# Stripline_Driver.net
KiCad netlist of a schematic drawn in Altium Designer
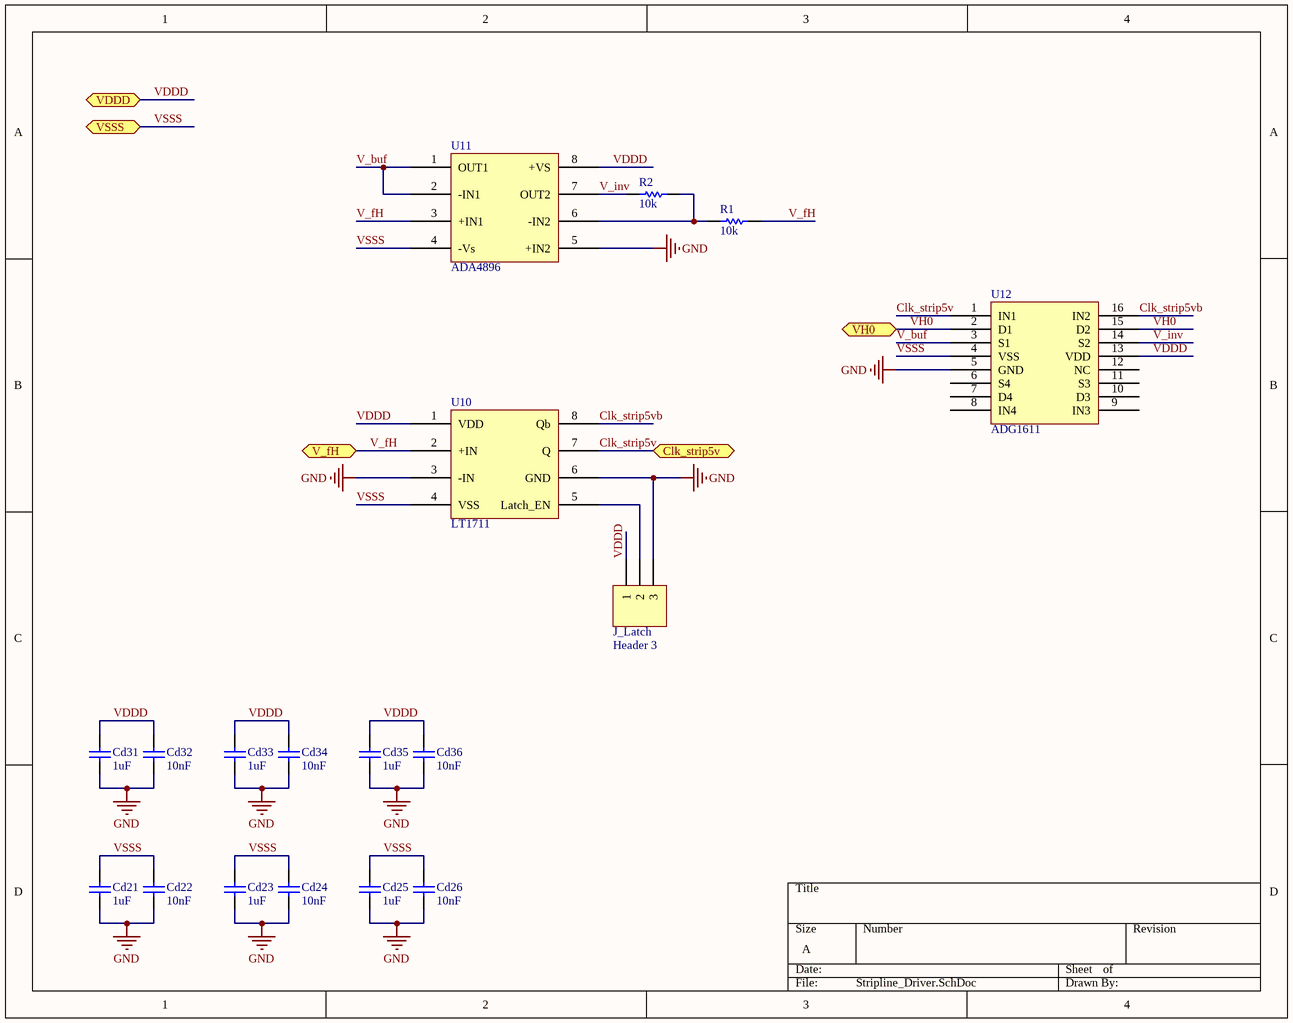
[diagram p0: Stripline_Driver.SchDoc]

(export (version "E")
  (design (tool "Eeschema 10.0.6"))
  (components
    (comp (ref "Cd21")
      (value "1uF")
      (footprint "1608[0603]")
      (description "Capacitor")
      (fields (field (name "Comment") "Cap") (field (name "PUBLISHER") "Altium Limited"))
      (libsource (lib "Miscellaneous Devices") (part "Cap"))
    )
    (comp (ref "Cd22")
      (value "10nF")
      (footprint "1608[0603]")
      (description "Capacitor")
      (fields (field (name "Comment") "Cap") (field (name "PUBLISHER") "Altium Limited"))
      (libsource (lib "Miscellaneous Devices") (part "Cap"))
    )
    (comp (ref "Cd23")
      (value "1uF")
      (footprint "1608[0603]")
      (description "Capacitor")
      (fields (field (name "Comment") "Cap") (field (name "PUBLISHER") "Altium Limited"))
      (libsource (lib "Miscellaneous Devices") (part "Cap"))
    )
    (comp (ref "Cd24")
      (value "10nF")
      (footprint "1608[0603]")
      (description "Capacitor")
      (fields (field (name "Comment") "Cap") (field (name "PUBLISHER") "Altium Limited"))
      (libsource (lib "Miscellaneous Devices") (part "Cap"))
    )
    (comp (ref "Cd25")
      (value "1uF")
      (footprint "1608[0603]")
      (description "Capacitor")
      (fields (field (name "Comment") "Cap") (field (name "PUBLISHER") "Altium Limited"))
      (libsource (lib "Miscellaneous Devices") (part "Cap"))
    )
    (comp (ref "Cd26")
      (value "10nF")
      (footprint "1608[0603]")
      (description "Capacitor")
      (fields (field (name "Comment") "Cap") (field (name "PUBLISHER") "Altium Limited"))
      (libsource (lib "Miscellaneous Devices") (part "Cap"))
    )
    (comp (ref "Cd31")
      (value "1uF")
      (footprint "1608[0603]")
      (description "Capacitor")
      (fields (field (name "Comment") "Cap") (field (name "PUBLISHER") "Altium Limited"))
      (libsource (lib "Miscellaneous Devices") (part "Cap"))
    )
    (comp (ref "Cd32")
      (value "10nF")
      (footprint "1608[0603]")
      (description "Capacitor")
      (fields (field (name "Comment") "Cap") (field (name "PUBLISHER") "Altium Limited"))
      (libsource (lib "Miscellaneous Devices") (part "Cap"))
    )
    (comp (ref "Cd33")
      (value "1uF")
      (footprint "1608[0603]")
      (description "Capacitor")
      (fields (field (name "Comment") "Cap") (field (name "PUBLISHER") "Altium Limited"))
      (libsource (lib "Miscellaneous Devices") (part "Cap"))
    )
    (comp (ref "Cd34")
      (value "10nF")
      (footprint "1608[0603]")
      (description "Capacitor")
      (fields (field (name "Comment") "Cap") (field (name "PUBLISHER") "Altium Limited"))
      (libsource (lib "Miscellaneous Devices") (part "Cap"))
    )
    (comp (ref "Cd35")
      (value "1uF")
      (footprint "1608[0603]")
      (description "Capacitor")
      (fields (field (name "Comment") "Cap") (field (name "PUBLISHER") "Altium Limited"))
      (libsource (lib "Miscellaneous Devices") (part "Cap"))
    )
    (comp (ref "Cd36")
      (value "10nF")
      (footprint "1608[0603]")
      (description "Capacitor")
      (fields (field (name "Comment") "Cap") (field (name "PUBLISHER") "Altium Limited"))
      (libsource (lib "Miscellaneous Devices") (part "Cap"))
    )
    (comp (ref "J_Latch")
      (value "Header 3")
      (footprint "HDR1X3")
      (description "Header, 3-Pin")
      (fields (field (name "PUBLISHER") "Altium Limited"))
      (libsource (lib "Miscellaneous Connectors") (part "Header 3"))
    )
    (comp (ref "R1")
      (value "10k")
      (footprint "1608[0603]")
      (description "Resistor")
      (fields (field (name "Comment") "Res1") (field (name "PUBLISHER") "Altium Limited"))
      (libsource (lib "Miscellaneous Devices") (part "Res1"))
    )
    (comp (ref "R2")
      (value "10k")
      (footprint "1608[0603]")
      (description "Resistor")
      (fields (field (name "Comment") "Res1") (field (name "PUBLISHER") "Altium Limited"))
      (libsource (lib "Miscellaneous Devices") (part "Res1"))
    )
    (comp (ref "U10") (value "LT1711") (footprint "RM-8") (libsource (lib "custom") (part "LT1711")))
    (comp (ref "U11") (value "ADA4896") (footprint "RM-8") (libsource (lib "custom") (part "ADA4862")))
    (comp (ref "U12") (value "ADG1611") (footprint "RU-16") (libsource (lib "custom") (part "ADG1611")))
  )
  (nets
    (net (code "1") (name "/Clk_strip5v") (class "Default")
      (node (ref "U10") (pin "7") (pinfunction "Q_7") (pintype "passive"))
      (node (ref "U12") (pin "1") (pinfunction "IN1_1") (pintype "passive"))
    )
    (net (code "2") (name "/Clk_strip5vb") (class "Default")
      (node (ref "U10") (pin "8") (pinfunction "Qb_8") (pintype "passive"))
      (node (ref "U12") (pin "16") (pinfunction "IN2_16") (pintype "passive"))
    )
    (net (code "3") (name "/VDDD") (class "Default")
      (node (ref "Cd31") (pin "1") (pinfunction "1_1") (pintype "passive"))
      (node (ref "Cd32") (pin "1") (pinfunction "1_1") (pintype "passive"))
      (node (ref "Cd33") (pin "1") (pinfunction "1_1") (pintype "passive"))
      (node (ref "Cd34") (pin "1") (pinfunction "1_1") (pintype "passive"))
      (node (ref "Cd35") (pin "1") (pinfunction "1_1") (pintype "passive"))
      (node (ref "Cd36") (pin "1") (pinfunction "1_1") (pintype "passive"))
      (node (ref "J_Latch") (pin "1") (pinfunction "1_1") (pintype "passive"))
      (node (ref "U10") (pin "1") (pinfunction "VDD_1") (pintype "passive"))
      (node (ref "U11") (pin "8") (pinfunction "+VS_8") (pintype "passive"))
      (node (ref "U12") (pin "13") (pinfunction "VDD_13") (pintype "passive"))
    )
    (net (code "4") (name "/VH0") (class "Default")
      (node (ref "U12") (pin "15") (pinfunction "D2_15") (pintype "passive"))
      (node (ref "U12") (pin "2") (pinfunction "D1_2") (pintype "passive"))
    )
    (net (code "5") (name "/VSSS") (class "Default")
      (node (ref "Cd21") (pin "1") (pinfunction "1_1") (pintype "passive"))
      (node (ref "Cd22") (pin "1") (pinfunction "1_1") (pintype "passive"))
      (node (ref "Cd23") (pin "1") (pinfunction "1_1") (pintype "passive"))
      (node (ref "Cd24") (pin "1") (pinfunction "1_1") (pintype "passive"))
      (node (ref "Cd25") (pin "1") (pinfunction "1_1") (pintype "passive"))
      (node (ref "Cd26") (pin "1") (pinfunction "1_1") (pintype "passive"))
      (node (ref "U10") (pin "4") (pinfunction "VSS_4") (pintype "passive"))
      (node (ref "U11") (pin "4") (pinfunction "-Vs_4") (pintype "passive"))
      (node (ref "U12") (pin "4") (pinfunction "VSS_4") (pintype "passive"))
    )
    (net (code "6") (name "/V_buf") (class "Default")
      (node (ref "U11") (pin "1") (pinfunction "OUT1_1") (pintype "passive"))
      (node (ref "U11") (pin "2") (pinfunction "-IN1_2") (pintype "passive"))
      (node (ref "U12") (pin "3") (pinfunction "S1_3") (pintype "passive"))
    )
    (net (code "7") (name "/V_fH") (class "Default")
      (node (ref "R1") (pin "2") (pinfunction "2_2") (pintype "passive"))
      (node (ref "U10") (pin "2") (pinfunction "+IN_2") (pintype "passive"))
      (node (ref "U11") (pin "3") (pinfunction "+IN1_3") (pintype "passive"))
    )
    (net (code "8") (name "/V_inv") (class "Default")
      (node (ref "R2") (pin "2") (pinfunction "2_2") (pintype "passive"))
      (node (ref "U11") (pin "7") (pinfunction "OUT2_7") (pintype "passive"))
      (node (ref "U12") (pin "14") (pinfunction "S2_14") (pintype "passive"))
    )
    (net (code "9") (name "GND") (class "Default")
      (node (ref "Cd21") (pin "2") (pinfunction "2_2") (pintype "passive"))
      (node (ref "Cd22") (pin "2") (pinfunction "2_2") (pintype "passive"))
      (node (ref "Cd23") (pin "2") (pinfunction "2_2") (pintype "passive"))
      (node (ref "Cd24") (pin "2") (pinfunction "2_2") (pintype "passive"))
      (node (ref "Cd25") (pin "2") (pinfunction "2_2") (pintype "passive"))
      (node (ref "Cd26") (pin "2") (pinfunction "2_2") (pintype "passive"))
      (node (ref "Cd31") (pin "2") (pinfunction "2_2") (pintype "passive"))
      (node (ref "Cd32") (pin "2") (pinfunction "2_2") (pintype "passive"))
      (node (ref "Cd33") (pin "2") (pinfunction "2_2") (pintype "passive"))
      (node (ref "Cd34") (pin "2") (pinfunction "2_2") (pintype "passive"))
      (node (ref "Cd35") (pin "2") (pinfunction "2_2") (pintype "passive"))
      (node (ref "Cd36") (pin "2") (pinfunction "2_2") (pintype "passive"))
      (node (ref "J_Latch") (pin "3") (pinfunction "3_3") (pintype "passive"))
      (node (ref "U10") (pin "3") (pinfunction "-IN_3") (pintype "passive"))
      (node (ref "U10") (pin "6") (pinfunction "GND_6") (pintype "passive"))
      (node (ref "U11") (pin "5") (pinfunction "+IN2_5") (pintype "passive"))
      (node (ref "U12") (pin "5") (pinfunction "GND_5") (pintype "passive"))
    )
    (net (code "10") (name "Net-(U10-Latch_EN)") (class "Default")
      (node (ref "J_Latch") (pin "2") (pinfunction "2_2") (pintype "passive"))
      (node (ref "U10") (pin "5") (pinfunction "Latch_EN_5") (pintype "passive"))
    )
    (net (code "11") (name "Net-(U11--IN2)") (class "Default")
      (node (ref "R1") (pin "1") (pinfunction "1_1") (pintype "passive"))
      (node (ref "R2") (pin "1") (pinfunction "1_1") (pintype "passive"))
      (node (ref "U11") (pin "6") (pinfunction "-IN2_6") (pintype "passive"))
    )
    (net (code "12") (name "unconnected-(U12-D3-Pad10)") (class "Default")
      (node (ref "U12") (pin "10") (pinfunction "D3_10") (pintype "passive"))
    )
    (net (code "13") (name "unconnected-(U12-D4-Pad7)") (class "Default")
      (node (ref "U12") (pin "7") (pinfunction "D4_7") (pintype "passive"))
    )
    (net (code "14") (name "unconnected-(U12-IN3-Pad9)") (class "Default")
      (node (ref "U12") (pin "9") (pinfunction "IN3_9") (pintype "passive"))
    )
    (net (code "15") (name "unconnected-(U12-IN4-Pad8)") (class "Default")
      (node (ref "U12") (pin "8") (pinfunction "IN4_8") (pintype "passive"))
    )
    (net (code "16") (name "unconnected-(U12-NC-Pad12)") (class "Default")
      (node (ref "U12") (pin "12") (pinfunction "NC_12") (pintype "passive"))
    )
    (net (code "17") (name "unconnected-(U12-S3-Pad11)") (class "Default")
      (node (ref "U12") (pin "11") (pinfunction "S3_11") (pintype "passive"))
    )
    (net (code "18") (name "unconnected-(U12-S4-Pad6)") (class "Default")
      (node (ref "U12") (pin "6") (pinfunction "S4_6") (pintype "passive"))
    )
  )
)
